# EEG_Electrodes.net
KiCad netlist of a schematic drawn in Altium Designer
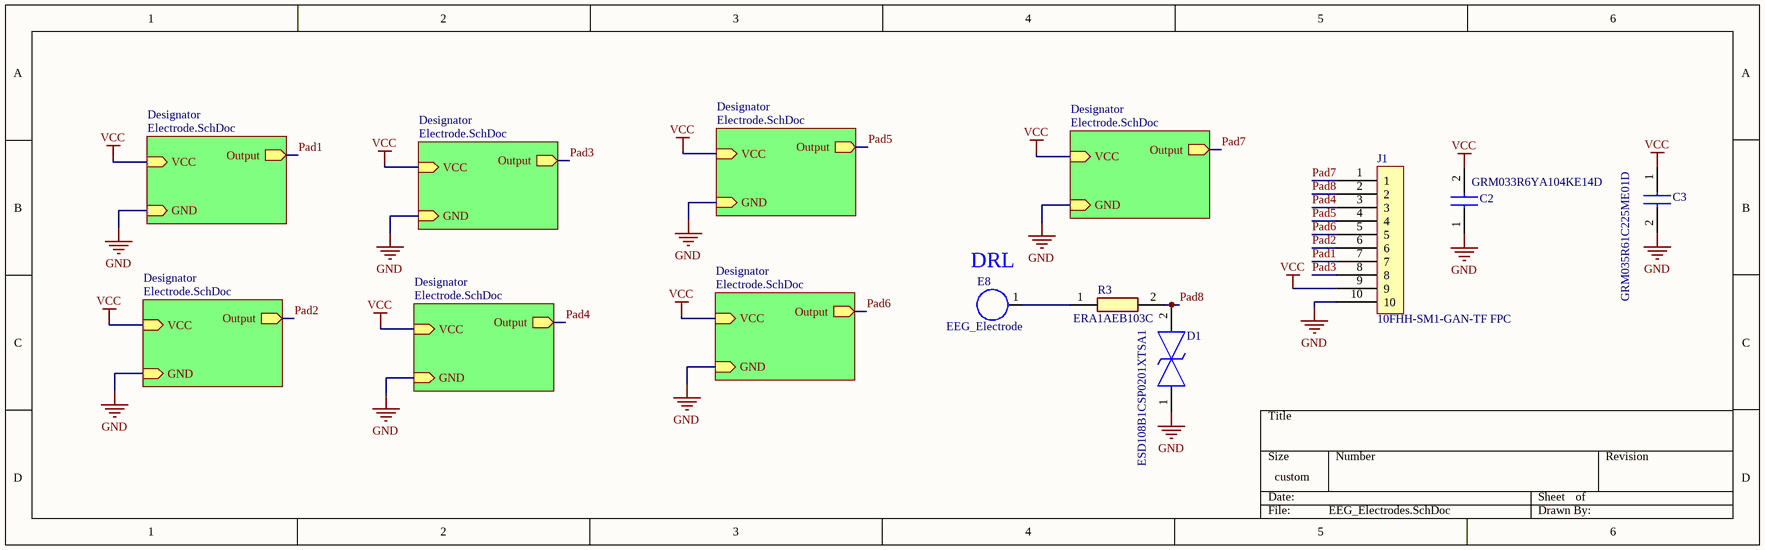
[diagram p0: EEG_Electrodes.SchDoc]

(export (version "E")
  (design (tool "Eeschema 10.0.6"))
  (components
    (comp (ref "C2")
      (value "GRM033R6YA104KE14D")
      (footprint "SamacSys:CAPC0603X33N")
      (description "Capacitor 0.1uF 0201")
      (fields (field (name "MOUSER PART NUMBER") "81-GRM33R6YA104KE14D"))
      (libsource (lib "*") (part "GRM033R6YA104KE14D"))
    )
    (comp (ref "C3")
      (value "GRM035R61C225ME01D")
      (footprint "SamacSys:GRM033D70J224ME01D")
      (description "Capacitor 2.2uF 0201")
      (fields (field (name "MOUSER PART NUMBER") "81-GRM035R61C225ME1D"))
      (libsource (lib "SamacSys") (part "GRM035R61C225ME01D"))
    )
    (comp (ref "D1")
      (value "ESD108B1CSP0201XTSA1")
      (footprint "SamacSys:ESD108B1CSP0201XTSA1")
      (description "TVS Diode (Bi-directional)")
      (fields (field (name "MOUSER PART NUMBER") "726-ESD108B1CSP0201X"))
      (libsource (lib "SamacSys") (part "ESD108B1CSP0201XTSA1"))
    )
    (comp (ref "E8")
      (value "EEG_Electrode")
      (footprint "EEG_Electrode")
      (libsource (lib "Rishabh_Schematic_Library") (part "EEG_Electrode"))
    )
    (comp (ref "J1")
      (value "10FHH-SM1-GAN-TF FPC")
      (footprint "10FHH-SM1-GAN-TF FPC")
      (libsource (lib "Rishabh_Schematic_Library") (part "10FHH-SM1-GAN-TF FPC"))
    )
    (comp (ref "R3")
      (value "ERA1AEB103C")
      (footprint "SamacSys:ERA1A_(0201)")
      (description "Resistor 10k")
      (libsource (lib "SamacSys") (part "ERA1AEB103C"))
    )
  )
  (nets
    (net (code "1") (name "/Pad1") (class "Default")
      (node (ref "J1") (pin "7") (pinfunction "7_7") (pintype "passive"))
    )
    (net (code "2") (name "/Pad2") (class "Default")
      (node (ref "J1") (pin "6") (pinfunction "6_6") (pintype "passive"))
    )
    (net (code "3") (name "/Pad3") (class "Default")
      (node (ref "J1") (pin "8") (pinfunction "8_8") (pintype "passive"))
    )
    (net (code "4") (name "/Pad4") (class "Default")
      (node (ref "J1") (pin "3") (pinfunction "3_3") (pintype "passive"))
    )
    (net (code "5") (name "/Pad5") (class "Default")
      (node (ref "J1") (pin "4") (pinfunction "4_4") (pintype "passive"))
    )
    (net (code "6") (name "/Pad6") (class "Default")
      (node (ref "J1") (pin "5") (pinfunction "5_5") (pintype "passive"))
    )
    (net (code "7") (name "/Pad7") (class "Default")
      (node (ref "J1") (pin "1") (pinfunction "1_1") (pintype "passive"))
    )
    (net (code "8") (name "/Pad8") (class "Default")
      (node (ref "D1") (pin "2") (pinfunction "2_2") (pintype "passive"))
      (node (ref "J1") (pin "2") (pinfunction "2_2") (pintype "passive"))
      (node (ref "R3") (pin "2") (pinfunction "2_2") (pintype "passive"))
    )
    (net (code "9") (name "GND") (class "Default")
      (node (ref "C2") (pin "1") (pinfunction "1_1") (pintype "passive"))
      (node (ref "C3") (pin "2") (pinfunction "2_2") (pintype "passive"))
      (node (ref "D1") (pin "1") (pinfunction "1_1") (pintype "passive"))
      (node (ref "J1") (pin "10") (pinfunction "10_10") (pintype "passive"))
    )
    (net (code "10") (name "Net-(E8-Pad1)") (class "Default")
      (node (ref "E8") (pin "1") (pintype "passive"))
      (node (ref "R3") (pin "1") (pinfunction "1_1") (pintype "passive"))
    )
    (net (code "11") (name "VCC") (class "Default")
      (node (ref "C2") (pin "2") (pinfunction "2_2") (pintype "passive"))
      (node (ref "C3") (pin "1") (pinfunction "1_1") (pintype "passive"))
      (node (ref "J1") (pin "9") (pinfunction "9_9") (pintype "passive"))
    )
  )
)
